# switch-esp01.net
KiCad netlist of a schematic drawn in Altium Designer
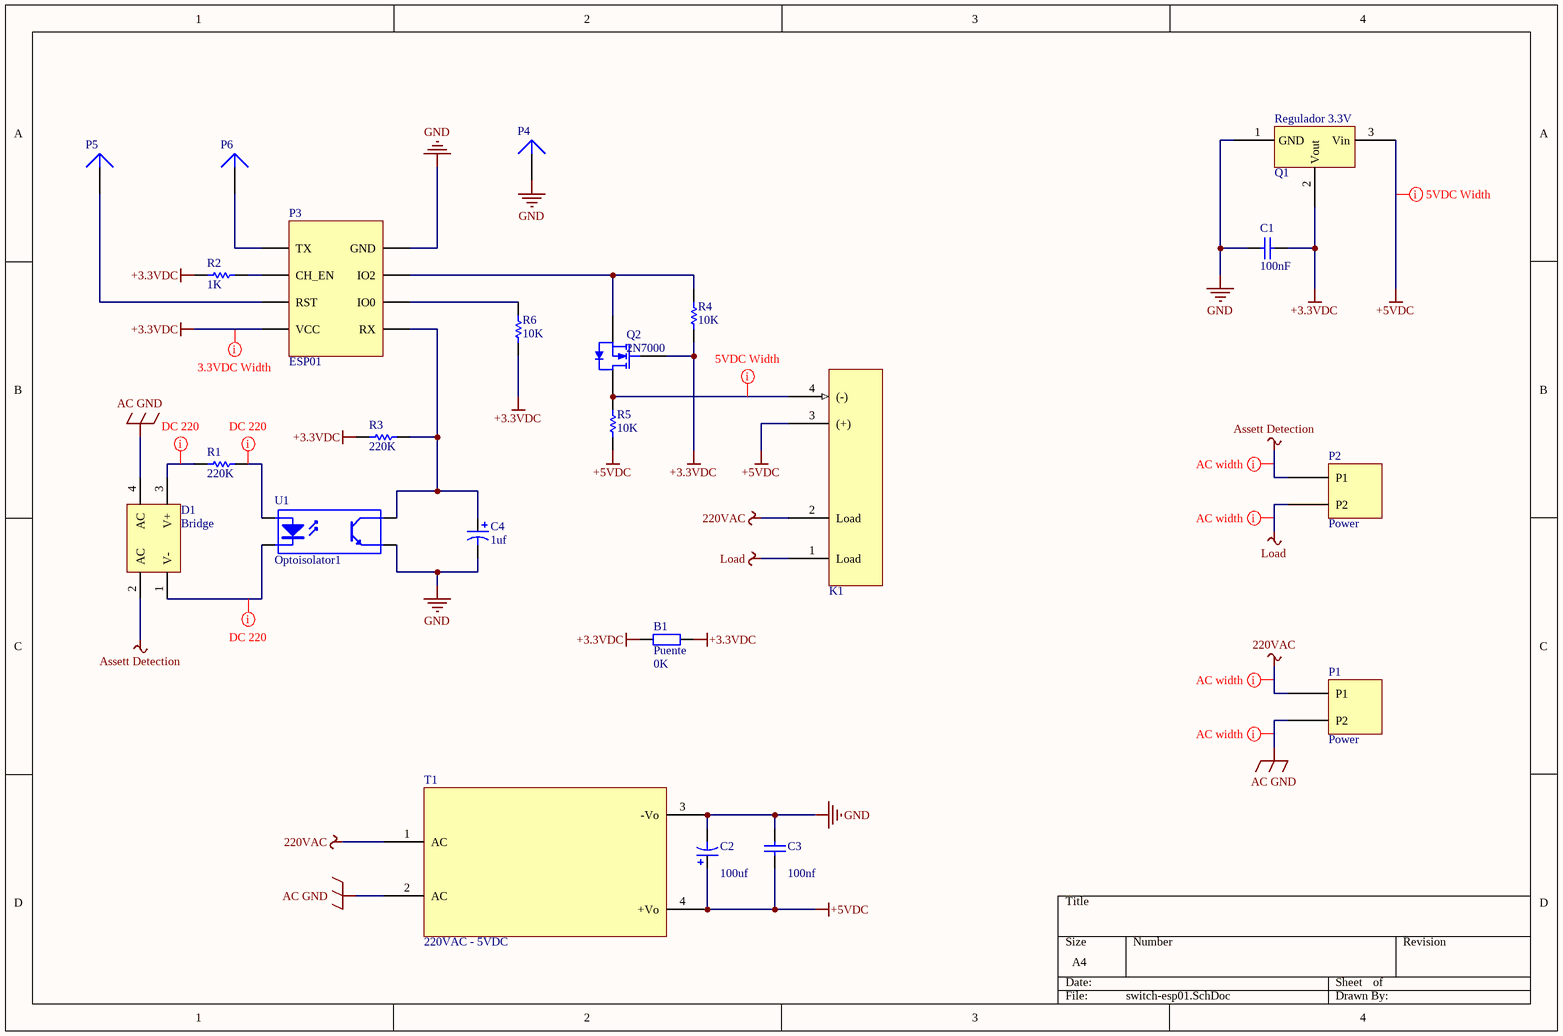
[diagram p0: switch-esp01.SchDoc]

(export (version "E")
  (design (tool "Eeschema 10.0.6"))
  (components
    (comp (ref "B1")
      (value "Puente")
      (footprint "AXIAL-0.4")
      (description "Resistor")
      (fields (field (name "ALTIUM_VALUE") "0K") (field (name "PUBLISHER") "Altium Limited"))
      (libsource (lib "Miscellaneous Devices") (part "Res2"))
    )
    (comp (ref "C1")
      (value "100nF")
      (footprint "RAD-0.1")
      (description "Capacitor")
      (fields (field (name "Comment") "100nf") (field (name "PUBLISHER") "Altium Limited"))
      (libsource (lib "Miscellaneous Devices") (part "Cap"))
    )
    (comp (ref "C2")
      (value "100uf")
      (footprint "RAD-0.1")
      (description "Polarized Capacitor (Radial)")
      (fields (field (name "Comment") "Cap Pol1") (field (name "PUBLISHER") "Altium Limited"))
      (libsource (lib "Miscellaneous Devices") (part "Cap Pol1"))
    )
    (comp (ref "C3")
      (value "100nf")
      (footprint "RAD-0.1")
      (description "Capacitor")
      (fields (field (name "Comment") "Cap") (field (name "PUBLISHER") "Altium Limited"))
      (libsource (lib "Miscellaneous Devices") (part "Cap"))
    )
    (comp (ref "C4")
      (value "1uf")
      (footprint "RAD-0.1")
      (description "Polarized Capacitor (Radial)")
      (fields (field (name "Comment") "Cap Pol1") (field (name "PUBLISHER") "Altium Limited"))
      (libsource (lib "Miscellaneous Devices") (part "Cap Pol1"))
    )
    (comp (ref "D1")
      (value "Bridge")
      (footprint "DB157")
      (description "Diode Bridge")
      (fields (field (name "PUBLISHER") "Altium Limited"))
      (libsource (lib "Miscellaneous Devices") (part "Bridge2"))
    )
    (comp (ref "K1")
      (value "G3MB-202P DC5")
      (footprint "G3MB-202P DC5")
      (description "RELAY MINI SSR 240VAC@2A ZERO")
      (fields (field (name "MFR") "Omron"))
      (libsource (lib "G3MB-202P") (part "G3MB-202P DC5"))
    )
    (comp (ref "P1")
      (value "Power")
      (footprint "ScrewTerminal-X2")
      (libsource (lib "ScrewTerminal_2X") (part "ScrewTerminal"))
    )
    (comp (ref "P2")
      (value "Power")
      (footprint "ScrewTerminal-X2")
      (libsource (lib "ScrewTerminal_2X") (part "ScrewTerminal"))
    )
    (comp (ref "P3") (value "ESP01") (footprint "HDR2X4") (libsource (lib "ESP01") (part "ESP01")))
    (comp (ref "P4")
      (value "Plug")
      (footprint "PIN1")
      (fields (field (name "PUBLISHER") "Altium Limited"))
      (libsource (lib "Miscellaneous Connectors") (part "Plug"))
    )
    (comp (ref "P5")
      (value "Plug")
      (footprint "PIN1")
      (fields (field (name "PUBLISHER") "Altium Limited"))
      (libsource (lib "Miscellaneous Connectors") (part "Plug"))
    )
    (comp (ref "P6")
      (value "Plug")
      (footprint "PIN1")
      (fields (field (name "PUBLISHER") "Altium Limited"))
      (libsource (lib "Miscellaneous Connectors") (part "Plug"))
    )
    (comp (ref "Q1")
      (value "Regulador 3.3V")
      (footprint "TO-220-AB")
      (libsource (lib "AMS1117") (part "AMS1117"))
    )
    (comp (ref "Q2")
      (value "2N7000")
      (footprint "TO-92-big_footprint:TO-92 BF")
      (description "N-channel Enhancement Mode Field-effect Transistor")
      (fields (field (name "PUBLISHER") "Altium Limited"))
      (libsource (lib "Philips Discrete MOSFET - Low Power") (part "2N7000"))
    )
    (comp (ref "R1")
      (value "220K")
      (footprint "AXIAL-0.3")
      (description "Resistor")
      (fields (field (name "Comment") "10K") (field (name "PUBLISHER") "Altium Limited"))
      (libsource (lib "Miscellaneous Devices") (part "Res1"))
    )
    (comp (ref "R2")
      (value "1K")
      (footprint "AXIAL-0.3")
      (description "Resistor")
      (fields (field (name "Comment") "10K") (field (name "PUBLISHER") "Altium Limited"))
      (libsource (lib "Miscellaneous Devices") (part "Res1"))
    )
    (comp (ref "R3")
      (value "220K")
      (footprint "AXIAL-0.3")
      (description "Resistor")
      (fields (field (name "Comment") "10K") (field (name "PUBLISHER") "Altium Limited"))
      (libsource (lib "Miscellaneous Devices") (part "Res1"))
    )
    (comp (ref "R4")
      (value "10K")
      (footprint "AXIAL-0.3")
      (description "Resistor")
      (fields (field (name "PUBLISHER") "Altium Limited"))
      (libsource (lib "Miscellaneous Devices") (part "Res1"))
    )
    (comp (ref "R5")
      (value "10K")
      (footprint "AXIAL-0.3")
      (description "Resistor")
      (fields (field (name "PUBLISHER") "Altium Limited"))
      (libsource (lib "Miscellaneous Devices") (part "Res1"))
    )
    (comp (ref "R6")
      (value "10K")
      (footprint "AXIAL-0.3")
      (description "Resistor")
      (fields (field (name "PUBLISHER") "Altium Limited"))
      (libsource (lib "Miscellaneous Devices") (part "Res1"))
    )
    (comp (ref "T1")
      (value "220VAC - 5VDC")
      (footprint "HLK-PM")
      (description "HLK-PM*")
      (fields (field (name "MFR") "HLK-PM01"))
      (libsource (lib "HLK-PM") (part "HLK-PM"))
    )
    (comp (ref "U1")
      (value "Optoisolator1")
      (footprint "DIP-4")
      (description "4-Pin Phototransistor Optocoupler")
      (fields (field (name "PUBLISHER") "Altium Limited"))
      (libsource (lib "Miscellaneous Devices") (part "Optoisolator1"))
    )
  )
  (nets
    (net (code "1") (name "+3.3VDC") (class "Default")
      (node (ref "B1") (pin "1") (pinfunction "1_1") (pintype "passive"))
      (node (ref "B1") (pin "2") (pinfunction "2_2") (pintype "passive"))
      (node (ref "C1") (pin "2") (pinfunction "2_2") (pintype "passive"))
      (node (ref "P3") (pin "4") (pinfunction "VCC_4") (pintype "passive"))
      (node (ref "Q1") (pin "2") (pinfunction "Vout_2") (pintype "passive"))
      (node (ref "Q2") (pin "2") (pinfunction "G_2") (pintype "passive"))
      (node (ref "R2") (pin "1") (pinfunction "1_1") (pintype "passive"))
      (node (ref "R3") (pin "1") (pinfunction "1_1") (pintype "passive"))
      (node (ref "R4") (pin "2") (pinfunction "2_2") (pintype "passive"))
      (node (ref "R6") (pin "1") (pinfunction "1_1") (pintype "passive"))
    )
    (net (code "2") (name "+5VDC") (class "Default")
      (node (ref "C2") (pin "1") (pinfunction "1_1") (pintype "passive"))
      (node (ref "C3") (pin "1") (pinfunction "1_1") (pintype "passive"))
      (node (ref "K1") (pin "3") (pinfunction "(+)_3") (pintype "power_in"))
      (node (ref "Q1") (pin "3") (pinfunction "Vin_3") (pintype "passive"))
      (node (ref "R5") (pin "2") (pinfunction "2_2") (pintype "passive"))
      (node (ref "T1") (pin "4") (pinfunction "+Vo_4") (pintype "passive"))
    )
    (net (code "3") (name "220VAC") (class "Default")
      (node (ref "K1") (pin "2") (pinfunction "Load_2") (pintype "passive"))
      (node (ref "P1") (pin "1") (pinfunction "P1_1") (pintype "passive"))
      (node (ref "T1") (pin "1") (pinfunction "AC_1") (pintype "power_in"))
    )
    (net (code "4") (name "AC GND") (class "Default")
      (node (ref "D1") (pin "4") (pinfunction "AC_4") (pintype "passive"))
      (node (ref "P1") (pin "2") (pinfunction "P2_2") (pintype "passive"))
      (node (ref "T1") (pin "2") (pinfunction "AC_2") (pintype "power_in"))
    )
    (net (code "5") (name "Assett Detection") (class "Default")
      (node (ref "D1") (pin "2") (pinfunction "AC_2") (pintype "passive"))
      (node (ref "P2") (pin "1") (pinfunction "P1_1") (pintype "passive"))
    )
    (net (code "6") (name "GND") (class "Default")
      (node (ref "C1") (pin "1") (pinfunction "1_1") (pintype "passive"))
      (node (ref "C2") (pin "2") (pinfunction "2_2") (pintype "passive"))
      (node (ref "C3") (pin "2") (pinfunction "2_2") (pintype "passive"))
      (node (ref "C4") (pin "2") (pinfunction "2_2") (pintype "passive"))
      (node (ref "P3") (pin "5") (pinfunction "GND_5") (pintype "passive"))
      (node (ref "P4") (pin "1") (pinfunction "1_1") (pintype "passive"))
      (node (ref "Q1") (pin "1") (pinfunction "GND_1") (pintype "passive"))
      (node (ref "T1") (pin "3") (pinfunction "-Vo_3") (pintype "passive"))
      (node (ref "U1") (pin "3") (pinfunction "E_3") (pintype "passive"))
    )
    (net (code "7") (name "Load") (class "Default")
      (node (ref "K1") (pin "1") (pinfunction "Load_1") (pintype "passive"))
      (node (ref "P2") (pin "2") (pinfunction "P2_2") (pintype "passive"))
    )
    (net (code "8") (name "Net-(D1-V+)") (class "Default")
      (node (ref "D1") (pin "3") (pinfunction "V+_3") (pintype "passive"))
      (node (ref "R1") (pin "1") (pinfunction "1_1") (pintype "passive"))
    )
    (net (code "9") (name "Net-(D1-V-)") (class "Default")
      (node (ref "D1") (pin "1") (pinfunction "V-_1") (pintype "passive"))
      (node (ref "U1") (pin "2") (pinfunction "K_2") (pintype "passive"))
    )
    (net (code "10") (name "Net-(K1-(-))") (class "Default")
      (node (ref "K1") (pin "4") (pinfunction "(-)_4") (pintype "input"))
      (node (ref "Q2") (pin "1") (pinfunction "D_1") (pintype "passive"))
      (node (ref "R5") (pin "1") (pinfunction "1_1") (pintype "passive"))
    )
    (net (code "11") (name "Net-(P3-CH_EN)") (class "Default")
      (node (ref "P3") (pin "2") (pinfunction "CH_EN_2") (pintype "passive"))
      (node (ref "R2") (pin "2") (pinfunction "2_2") (pintype "passive"))
    )
    (net (code "12") (name "Net-(P3-IO0)") (class "Default")
      (node (ref "P3") (pin "7") (pinfunction "IO0_7") (pintype "passive"))
      (node (ref "R6") (pin "2") (pinfunction "2_2") (pintype "passive"))
    )
    (net (code "13") (name "Net-(P3-IO2)") (class "Default")
      (node (ref "P3") (pin "6") (pinfunction "IO2_6") (pintype "passive"))
      (node (ref "Q2") (pin "3") (pinfunction "S_3") (pintype "passive"))
      (node (ref "R4") (pin "1") (pinfunction "1_1") (pintype "passive"))
    )
    (net (code "14") (name "Net-(P3-RST)") (class "Default")
      (node (ref "P3") (pin "3") (pinfunction "RST_3") (pintype "passive"))
      (node (ref "P5") (pin "1") (pinfunction "1_1") (pintype "passive"))
    )
    (net (code "15") (name "Net-(P3-RX)") (class "Default")
      (node (ref "C4") (pin "1") (pinfunction "1_1") (pintype "passive"))
      (node (ref "P3") (pin "8") (pinfunction "RX_8") (pintype "passive"))
      (node (ref "R3") (pin "2") (pinfunction "2_2") (pintype "passive"))
      (node (ref "U1") (pin "4") (pinfunction "C_4") (pintype "passive"))
    )
    (net (code "16") (name "Net-(P3-TX)") (class "Default")
      (node (ref "P3") (pin "1") (pinfunction "TX_1") (pintype "passive"))
      (node (ref "P6") (pin "1") (pinfunction "1_1") (pintype "passive"))
    )
    (net (code "17") (name "Net-(U1-A)") (class "Default")
      (node (ref "R1") (pin "2") (pinfunction "2_2") (pintype "passive"))
      (node (ref "U1") (pin "1") (pinfunction "A_1") (pintype "passive"))
    )
  )
)
